# dcdc_1_3_0304.net
KiCad netlist of a schematic drawn in EAGLE
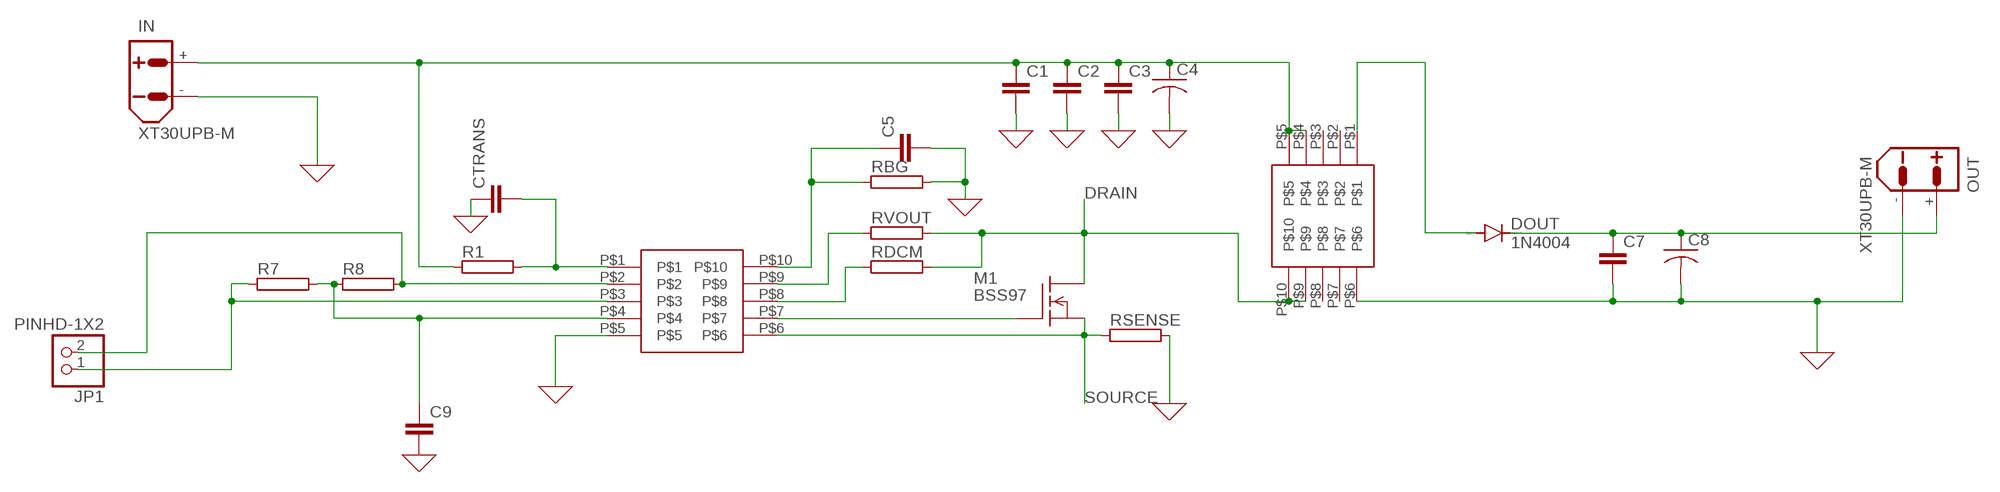
[diagram p0: schematic, sheet 1]

(export (version "E")
  (design (tool "Eeschema 10.0.6"))
  (components
    (comp (ref "C1")
      (value "C5/3.5")
      (footprint "eagle-import:C5B3.5")
      (libsource (lib "eagle-import") (part "C5/3.5"))
    )
    (comp (ref "C2")
      (value "C5/3.5")
      (footprint "eagle-import:C5B3.5")
      (libsource (lib "eagle-import") (part "C5/3.5"))
    )
    (comp (ref "C3")
      (value "C5/3.5")
      (footprint "eagle-import:C5B3.5")
      (libsource (lib "eagle-import") (part "C5/3.5"))
    )
    (comp (ref "C4")
      (value "C-US050-050X075")
      (footprint "eagle-import:C050-050X075")
      (libsource (lib "eagle-import") (part "C-US050-050X075"))
    )
    (comp (ref "C5")
      (value "C5/3.5")
      (footprint "eagle-import:C5B3.5")
      (libsource (lib "eagle-import") (part "C5/3.5"))
    )
    (comp (ref "C7")
      (value "C5/3.5")
      (footprint "eagle-import:C5B3.5")
      (libsource (lib "eagle-import") (part "C5/3.5"))
    )
    (comp (ref "C8")
      (value "C-US050-050X075")
      (footprint "eagle-import:C050-050X075")
      (libsource (lib "eagle-import") (part "C-US050-050X075"))
    )
    (comp (ref "C9")
      (value "C5/3.5")
      (footprint "eagle-import:C5B3.5")
      (libsource (lib "eagle-import") (part "C5/3.5"))
    )
    (comp (ref "CTRANS")
      (value "C5/3.5")
      (footprint "eagle-import:C5B3.5")
      (libsource (lib "eagle-import") (part "C5/3.5"))
    )
    (comp (ref "DOUT")
      (value "1N4004")
      (footprint "eagle-import:DO41-10")
      (libsource (lib "eagle-import") (part "1N4004"))
    )
    (comp (ref "IN")
      (value "XT30UPB-M")
      (footprint "eagle-import:XT30UPB-M")
      (libsource (lib "eagle-import") (part "XT30UPB-M"))
    )
    (comp (ref "JP1")
      (value "PINHD-1X2")
      (footprint "eagle-import:1X02")
      (libsource (lib "eagle-import") (part "PINHD-1X2"))
    )
    (comp (ref "M1")
      (value "BSS97")
      (footprint "eagle-import:TO202")
      (libsource (lib "eagle-import") (part "BSS97"))
    )
    (comp (ref "OUT")
      (value "XT30UPB-M")
      (footprint "eagle-import:XT30UPB-M")
      (libsource (lib "eagle-import") (part "XT30UPB-M"))
    )
    (comp (ref "R1")
      (value "RAC01")
      (footprint "eagle-import:AC01")
      (libsource (lib "eagle-import") (part "RAC01"))
    )
    (comp (ref "R7")
      (value "RAC01")
      (footprint "eagle-import:AC01")
      (libsource (lib "eagle-import") (part "RAC01"))
    )
    (comp (ref "R8")
      (value "RAC01")
      (footprint "eagle-import:AC01")
      (libsource (lib "eagle-import") (part "RAC01"))
    )
    (comp (ref "RBG")
      (value "RAC01")
      (footprint "eagle-import:AC01")
      (libsource (lib "eagle-import") (part "RAC01"))
    )
    (comp (ref "RDCM")
      (value "RAC01")
      (footprint "eagle-import:AC01")
      (libsource (lib "eagle-import") (part "RAC01"))
    )
    (comp (ref "RSENSE")
      (value "RAC01")
      (footprint "eagle-import:AC01")
      (libsource (lib "eagle-import") (part "RAC01"))
    )
    (comp (ref "RVOUT")
      (value "RAC01")
      (footprint "eagle-import:AC01")
      (libsource (lib "eagle-import") (part "RAC01"))
    )
    (comp (ref "U$1")
      (value "LT3750")
      (footprint "eagle-import:LT3750")
      (libsource (lib "eagle-import") (part "LT3750"))
    )
    (comp (ref "U$2")
      (value "32052")
      (footprint "eagle-import:32052")
      (libsource (lib "eagle-import") (part "32052"))
    )
  )
  (nets
    (net (code "1") (name "/DRAIN") (class "Default")
      (node (ref "M1") (pin "2") (pinfunction "D_2") (pintype "passive"))
      (node (ref "RDCM") (pin "2") (pinfunction "2_2") (pintype "passive"))
      (node (ref "RVOUT") (pin "2") (pinfunction "2_2") (pintype "passive"))
      (node (ref "U$2") (pin "P$10") (pinfunction "P$10_P$10") (pintype "bidirectional"))
      (node (ref "U$2") (pin "P$9") (pinfunction "P$9_P$9") (pintype "bidirectional"))
    )
    (net (code "2") (name "/SOURCE") (class "Default")
      (node (ref "M1") (pin "1") (pinfunction "S_1") (pintype "passive"))
      (node (ref "RSENSE") (pin "1") (pinfunction "1_1") (pintype "passive"))
      (node (ref "U$1") (pin "P$6") (pinfunction "P$6_P$6") (pintype "bidirectional"))
    )
    (net (code "3") (name "GND") (class "Default")
      (node (ref "C1") (pin "2") (pinfunction "2_2") (pintype "passive"))
      (node (ref "C2") (pin "2") (pinfunction "2_2") (pintype "passive"))
      (node (ref "C3") (pin "2") (pinfunction "2_2") (pintype "passive"))
      (node (ref "C4") (pin "2") (pinfunction "2_2") (pintype "passive"))
      (node (ref "C5") (pin "2") (pinfunction "2_2") (pintype "passive"))
      (node (ref "C7") (pin "2") (pinfunction "2_2") (pintype "passive"))
      (node (ref "C8") (pin "2") (pinfunction "2_2") (pintype "passive"))
      (node (ref "C9") (pin "2") (pinfunction "2_2") (pintype "passive"))
      (node (ref "CTRANS") (pin "1") (pinfunction "1_1") (pintype "passive"))
      (node (ref "IN") (pin "-") (pinfunction "-_-") (pintype "power_in"))
      (node (ref "OUT") (pin "-") (pinfunction "-_-") (pintype "power_in"))
      (node (ref "RBG") (pin "2") (pinfunction "2_2") (pintype "passive"))
      (node (ref "RSENSE") (pin "2") (pinfunction "2_2") (pintype "passive"))
      (node (ref "U$1") (pin "P$5") (pinfunction "P$5_P$5") (pintype "bidirectional"))
      (node (ref "U$2") (pin "P$6") (pinfunction "P$6_P$6") (pintype "bidirectional"))
    )
    (net (code "4") (name "Net-(C1-Pad1)") (class "Default")
      (node (ref "C1") (pin "1") (pinfunction "1_1") (pintype "passive"))
      (node (ref "C2") (pin "1") (pinfunction "1_1") (pintype "passive"))
      (node (ref "C3") (pin "1") (pinfunction "1_1") (pintype "passive"))
      (node (ref "C4") (pin "1") (pinfunction "1_1") (pintype "passive"))
      (node (ref "IN") (pin "+") (pinfunction "+_+") (pintype "power_in"))
      (node (ref "R1") (pin "1") (pinfunction "1_1") (pintype "passive"))
      (node (ref "U$2") (pin "P$4") (pinfunction "P$4_P$4") (pintype "bidirectional"))
      (node (ref "U$2") (pin "P$5") (pinfunction "P$5_P$5") (pintype "bidirectional"))
    )
    (net (code "5") (name "Net-(C5-Pad1)") (class "Default")
      (node (ref "C5") (pin "1") (pinfunction "1_1") (pintype "passive"))
      (node (ref "RBG") (pin "1") (pinfunction "1_1") (pintype "passive"))
      (node (ref "U$1") (pin "P$10") (pinfunction "P$10_P$10") (pintype "bidirectional"))
    )
    (net (code "6") (name "Net-(C7-Pad1)") (class "Default")
      (node (ref "C7") (pin "1") (pinfunction "1_1") (pintype "passive"))
      (node (ref "C8") (pin "1") (pinfunction "1_1") (pintype "passive"))
      (node (ref "DOUT") (pin "C") (pinfunction "C_C") (pintype "passive"))
      (node (ref "OUT") (pin "+") (pinfunction "+_+") (pintype "power_in"))
    )
    (net (code "7") (name "Net-(C9-Pad1)") (class "Default")
      (node (ref "C9") (pin "1") (pinfunction "1_1") (pintype "passive"))
      (node (ref "R7") (pin "2") (pinfunction "2_2") (pintype "passive"))
      (node (ref "R8") (pin "1") (pinfunction "1_1") (pintype "passive"))
      (node (ref "U$1") (pin "P$4") (pinfunction "P$4_P$4") (pintype "bidirectional"))
    )
    (net (code "8") (name "Net-(CTRANS-Pad2)") (class "Default")
      (node (ref "CTRANS") (pin "2") (pinfunction "2_2") (pintype "passive"))
      (node (ref "R1") (pin "2") (pinfunction "2_2") (pintype "passive"))
      (node (ref "U$1") (pin "P$1") (pinfunction "P$1_P$1") (pintype "bidirectional"))
    )
    (net (code "9") (name "Net-(DOUT-PadA)") (class "Default")
      (node (ref "DOUT") (pin "A") (pinfunction "A_A") (pintype "passive"))
      (node (ref "U$2") (pin "P$1") (pinfunction "P$1_P$1") (pintype "bidirectional"))
    )
    (net (code "10") (name "Net-(JP1-Pad1)") (class "Default")
      (node (ref "JP1") (pin "1") (pinfunction "1_1") (pintype "passive"))
      (node (ref "R7") (pin "1") (pinfunction "1_1") (pintype "passive"))
      (node (ref "U$1") (pin "P$3") (pinfunction "P$3_P$3") (pintype "bidirectional"))
    )
    (net (code "11") (name "Net-(JP1-Pad2)") (class "Default")
      (node (ref "JP1") (pin "2") (pinfunction "2_2") (pintype "passive"))
      (node (ref "R8") (pin "2") (pinfunction "2_2") (pintype "passive"))
      (node (ref "U$1") (pin "P$2") (pinfunction "P$2_P$2") (pintype "bidirectional"))
    )
    (net (code "12") (name "Net-(M1-G)") (class "Default")
      (node (ref "M1") (pin "3") (pinfunction "G_3") (pintype "passive"))
      (node (ref "U$1") (pin "P$7") (pinfunction "P$7_P$7") (pintype "bidirectional"))
    )
    (net (code "13") (name "Net-(RDCM-Pad1)") (class "Default")
      (node (ref "RDCM") (pin "1") (pinfunction "1_1") (pintype "passive"))
      (node (ref "U$1") (pin "P$8") (pinfunction "P$8_P$8") (pintype "bidirectional"))
    )
    (net (code "14") (name "Net-(RVOUT-Pad1)") (class "Default")
      (node (ref "RVOUT") (pin "1") (pinfunction "1_1") (pintype "passive"))
      (node (ref "U$1") (pin "P$9") (pinfunction "P$9_P$9") (pintype "bidirectional"))
    )
    (net (code "15") (name "unconnected-(U$2-PadP$2)") (class "Default")
      (node (ref "U$2") (pin "P$2") (pinfunction "P$2_P$2") (pintype "bidirectional"))
    )
    (net (code "16") (name "unconnected-(U$2-PadP$3)") (class "Default")
      (node (ref "U$2") (pin "P$3") (pinfunction "P$3_P$3") (pintype "bidirectional"))
    )
    (net (code "17") (name "unconnected-(U$2-PadP$7)") (class "Default")
      (node (ref "U$2") (pin "P$7") (pinfunction "P$7_P$7") (pintype "bidirectional"))
    )
    (net (code "18") (name "unconnected-(U$2-PadP$8)") (class "Default")
      (node (ref "U$2") (pin "P$8") (pinfunction "P$8_P$8") (pintype "bidirectional"))
    )
  )
)
